# dist_sensor.net
KiCad netlist of a schematic drawn in EAGLE
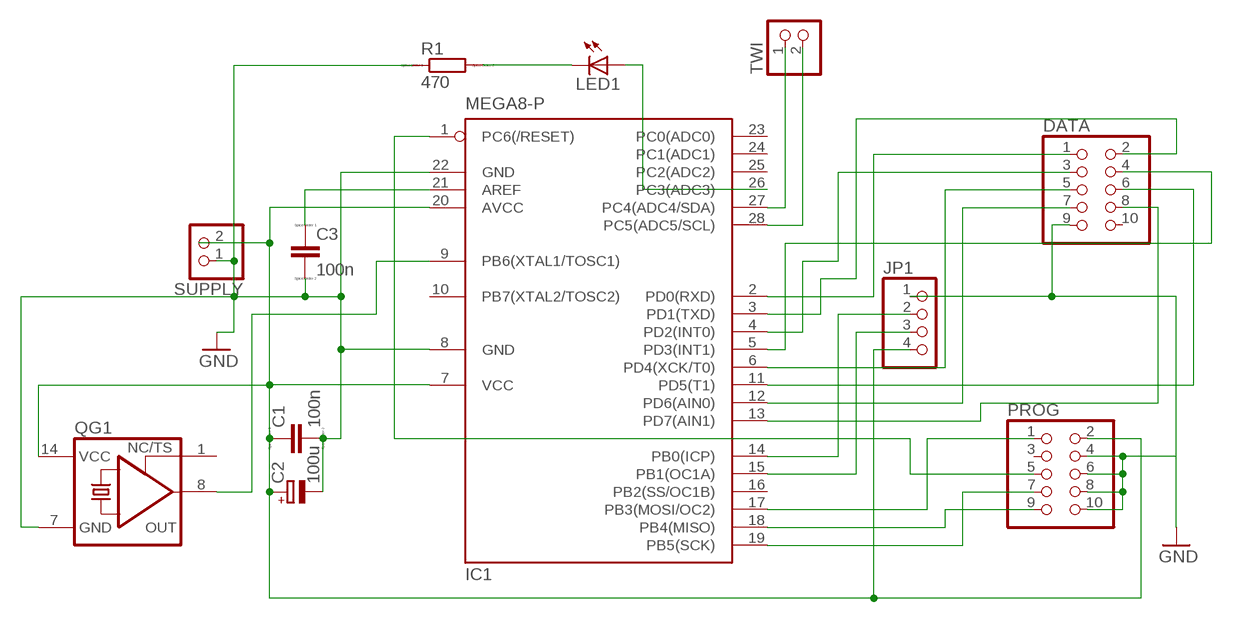
[diagram p0: schematic, sheet 1]

(export (version "E")
  (design (tool "Eeschema 10.0.6"))
  (components
    (comp (ref "C1")
      (value "100n")
      (footprint "eagle-import:C025-025X050")
      (libsource (lib "eagle-import") (part "C-EU025-025X050"))
    )
    (comp (ref "C2")
      (value "100u")
      (footprint "eagle-import:E5-8,5")
      (libsource (lib "eagle-import") (part "CPOL-EUE5-8.5"))
    )
    (comp (ref "C3")
      (value "100n")
      (footprint "eagle-import:C025-025X050")
      (libsource (lib "eagle-import") (part "C-EU025-025X050"))
    )
    (comp (ref "DATA")
      (value "PINHD-2X5")
      (footprint "eagle-import:2X05")
      (libsource (lib "eagle-import") (part "PINHD-2X5"))
    )
    (comp (ref "IC1")
      (value "MEGA8-P")
      (footprint "eagle-import:DIL28-3")
      (libsource (lib "eagle-import") (part "MEGA8-P"))
    )
    (comp (ref "JP1")
      (value "PINHD-1X4")
      (footprint "eagle-import:1X04")
      (libsource (lib "eagle-import") (part "PINHD-1X4"))
    )
    (comp (ref "LED1")
      (value "LED5MM")
      (footprint "eagle-import:LED5MM")
      (libsource (lib "eagle-import") (part "LED5MM"))
    )
    (comp (ref "PROG")
      (value "PINHD-2X5")
      (footprint "eagle-import:2X05")
      (libsource (lib "eagle-import") (part "PINHD-2X5"))
    )
    (comp (ref "QG1")
      (value "XO-14")
      (footprint "eagle-import:DIL14S")
      (libsource (lib "eagle-import") (part "XO-14"))
    )
    (comp (ref "R1")
      (value "470")
      (footprint "eagle-import:0207_10")
      (libsource (lib "eagle-import") (part "R-EU_0207_10"))
    )
    (comp (ref "SUPPLY")
      (value "PINHD-1X2")
      (footprint "eagle-import:1X02")
      (libsource (lib "eagle-import") (part "PINHD-1X2"))
    )
    (comp (ref "TWI")
      (value "PINHD-1X2")
      (footprint "eagle-import:1X02")
      (libsource (lib "eagle-import") (part "PINHD-1X2"))
    )
  )
  (nets
    (net (code "1") (name "GND") (class "Default")
      (node (ref "C1") (pin "2") (pinfunction "2_2") (pintype "passive"))
      (node (ref "C2") (pin "-") (pinfunction "-_-") (pintype "passive"))
      (node (ref "C3") (pin "2") (pinfunction "2_2") (pintype "passive"))
      (node (ref "DATA") (pin "9") (pinfunction "9_9") (pintype "passive"))
      (node (ref "IC1") (pin "22") (pinfunction "GND_22") (pintype "power_in"))
      (node (ref "IC1") (pin "8") (pinfunction "GND_8") (pintype "power_in"))
      (node (ref "JP1") (pin "1") (pinfunction "1_1") (pintype "passive"))
      (node (ref "PROG") (pin "10") (pinfunction "10_10") (pintype "passive"))
      (node (ref "PROG") (pin "4") (pinfunction "4_4") (pintype "passive"))
      (node (ref "PROG") (pin "6") (pinfunction "6_6") (pintype "passive"))
      (node (ref "PROG") (pin "8") (pinfunction "8_8") (pintype "passive"))
      (node (ref "QG1") (pin "7") (pinfunction "GND_7") (pintype "power_in"))
      (node (ref "R1") (pin "1") (pinfunction "1_1") (pintype "passive"))
      (node (ref "SUPPLY") (pin "1") (pinfunction "1_1") (pintype "passive"))
    )
    (net (code "2") (name "Net-(IC1-AREF)") (class "Default")
      (node (ref "C3") (pin "1") (pinfunction "1_1") (pintype "passive"))
      (node (ref "IC1") (pin "21") (pinfunction "AREF_21") (pintype "passive"))
    )
    (net (code "3") (name "Net-(IC1-AVCC)") (class "Default")
      (node (ref "C1") (pin "1") (pinfunction "1_1") (pintype "passive"))
      (node (ref "C2") (pin "+") (pinfunction "+_+") (pintype "passive"))
      (node (ref "IC1") (pin "20") (pinfunction "AVCC_20") (pintype "power_in"))
      (node (ref "IC1") (pin "7") (pinfunction "VCC_7") (pintype "power_in"))
      (node (ref "JP1") (pin "4") (pinfunction "4_4") (pintype "passive"))
      (node (ref "PROG") (pin "2") (pinfunction "2_2") (pintype "passive"))
      (node (ref "QG1") (pin "14") (pinfunction "VCC_14") (pintype "power_in"))
      (node (ref "SUPPLY") (pin "2") (pinfunction "2_2") (pintype "passive"))
    )
    (net (code "4") (name "Net-(IC1-PB0(ICP))") (class "Default")
      (node (ref "IC1") (pin "14") (pinfunction "PB0(ICP)_14") (pintype "bidirectional"))
      (node (ref "JP1") (pin "2") (pinfunction "2_2") (pintype "passive"))
    )
    (net (code "5") (name "Net-(IC1-PB1(OC1A))") (class "Default")
      (node (ref "IC1") (pin "15") (pinfunction "PB1(OC1A)_15") (pintype "bidirectional"))
      (node (ref "JP1") (pin "3") (pinfunction "3_3") (pintype "passive"))
    )
    (net (code "6") (name "Net-(IC1-PB3(MOSI{slash}OC2))") (class "Default")
      (node (ref "IC1") (pin "17") (pinfunction "PB3(MOSI/OC2)_17") (pintype "bidirectional"))
      (node (ref "PROG") (pin "1") (pinfunction "1_1") (pintype "passive"))
    )
    (net (code "7") (name "Net-(IC1-PB4(MISO))") (class "Default")
      (node (ref "IC1") (pin "18") (pinfunction "PB4(MISO)_18") (pintype "bidirectional"))
      (node (ref "PROG") (pin "9") (pinfunction "9_9") (pintype "passive"))
    )
    (net (code "8") (name "Net-(IC1-PB5(SCK))") (class "Default")
      (node (ref "IC1") (pin "19") (pinfunction "PB5(SCK)_19") (pintype "bidirectional"))
      (node (ref "PROG") (pin "7") (pinfunction "7_7") (pintype "passive"))
    )
    (net (code "9") (name "Net-(IC1-PB6(XTAL1{slash}TOSC1))") (class "Default")
      (node (ref "IC1") (pin "9") (pinfunction "PB6(XTAL1/TOSC1)_9") (pintype "bidirectional"))
      (node (ref "QG1") (pin "8") (pinfunction "OUT_8") (pintype "output"))
    )
    (net (code "10") (name "Net-(IC1-PC3(ADC3))") (class "Default")
      (node (ref "IC1") (pin "26") (pinfunction "PC3(ADC3)_26") (pintype "bidirectional"))
      (node (ref "LED1") (pin "A") (pinfunction "A_A") (pintype "passive"))
    )
    (net (code "11") (name "Net-(IC1-PC4(ADC4{slash}SDA))") (class "Default")
      (node (ref "IC1") (pin "27") (pinfunction "PC4(ADC4/SDA)_27") (pintype "bidirectional"))
      (node (ref "TWI") (pin "1") (pinfunction "1_1") (pintype "passive"))
    )
    (net (code "12") (name "Net-(IC1-PC5(ADC5{slash}SCL))") (class "Default")
      (node (ref "IC1") (pin "28") (pinfunction "PC5(ADC5/SCL)_28") (pintype "bidirectional"))
      (node (ref "TWI") (pin "2") (pinfunction "2_2") (pintype "passive"))
    )
    (net (code "13") (name "Net-(IC1-PC6({slash}RESET))") (class "Default")
      (node (ref "IC1") (pin "1") (pinfunction "PC6(/RESET)_1") (pintype "bidirectional"))
      (node (ref "PROG") (pin "5") (pinfunction "5_5") (pintype "passive"))
    )
    (net (code "14") (name "Net-(IC1-PD0(RXD))") (class "Default")
      (node (ref "DATA") (pin "1") (pinfunction "1_1") (pintype "passive"))
      (node (ref "IC1") (pin "2") (pinfunction "PD0(RXD)_2") (pintype "bidirectional"))
    )
    (net (code "15") (name "Net-(IC1-PD1(TXD))") (class "Default")
      (node (ref "DATA") (pin "2") (pinfunction "2_2") (pintype "passive"))
      (node (ref "IC1") (pin "3") (pinfunction "PD1(TXD)_3") (pintype "bidirectional"))
    )
    (net (code "16") (name "Net-(IC1-PD2(INT0))") (class "Default")
      (node (ref "DATA") (pin "3") (pinfunction "3_3") (pintype "passive"))
      (node (ref "IC1") (pin "4") (pinfunction "PD2(INT0)_4") (pintype "bidirectional"))
    )
    (net (code "17") (name "Net-(IC1-PD3(INT1))") (class "Default")
      (node (ref "DATA") (pin "4") (pinfunction "4_4") (pintype "passive"))
      (node (ref "IC1") (pin "5") (pinfunction "PD3(INT1)_5") (pintype "bidirectional"))
    )
    (net (code "18") (name "Net-(IC1-PD4(XCK{slash}T0))") (class "Default")
      (node (ref "DATA") (pin "5") (pinfunction "5_5") (pintype "passive"))
      (node (ref "IC1") (pin "6") (pinfunction "PD4(XCK/T0)_6") (pintype "bidirectional"))
    )
    (net (code "19") (name "Net-(IC1-PD5(T1))") (class "Default")
      (node (ref "DATA") (pin "6") (pinfunction "6_6") (pintype "passive"))
      (node (ref "IC1") (pin "11") (pinfunction "PD5(T1)_11") (pintype "bidirectional"))
    )
    (net (code "20") (name "Net-(IC1-PD6(AIN0))") (class "Default")
      (node (ref "DATA") (pin "7") (pinfunction "7_7") (pintype "passive"))
      (node (ref "IC1") (pin "12") (pinfunction "PD6(AIN0)_12") (pintype "bidirectional"))
    )
    (net (code "21") (name "Net-(IC1-PD7(AIN1))") (class "Default")
      (node (ref "DATA") (pin "8") (pinfunction "8_8") (pintype "passive"))
      (node (ref "IC1") (pin "13") (pinfunction "PD7(AIN1)_13") (pintype "bidirectional"))
    )
    (net (code "22") (name "Net-(LED1-C)") (class "Default")
      (node (ref "LED1") (pin "K") (pinfunction "C_K") (pintype "passive"))
      (node (ref "R1") (pin "2") (pinfunction "2_2") (pintype "passive"))
    )
    (net (code "23") (name "unconnected-(DATA-Pad10)") (class "Default")
      (node (ref "DATA") (pin "10") (pinfunction "10_10") (pintype "passive"))
    )
    (net (code "24") (name "unconnected-(IC1-PB2(SS{slash}OC1B)-Pad16)") (class "Default")
      (node (ref "IC1") (pin "16") (pinfunction "PB2(SS/OC1B)_16") (pintype "bidirectional"))
    )
    (net (code "25") (name "unconnected-(IC1-PB7(XTAL2{slash}TOSC2)-Pad10)") (class "Default")
      (node (ref "IC1") (pin "10") (pinfunction "PB7(XTAL2/TOSC2)_10") (pintype "bidirectional"))
    )
    (net (code "26") (name "unconnected-(IC1-PC0(ADC0)-Pad23)") (class "Default")
      (node (ref "IC1") (pin "23") (pinfunction "PC0(ADC0)_23") (pintype "bidirectional"))
    )
    (net (code "27") (name "unconnected-(IC1-PC1(ADC1)-Pad24)") (class "Default")
      (node (ref "IC1") (pin "24") (pinfunction "PC1(ADC1)_24") (pintype "bidirectional"))
    )
    (net (code "28") (name "unconnected-(IC1-PC2(ADC2)-Pad25)") (class "Default")
      (node (ref "IC1") (pin "25") (pinfunction "PC2(ADC2)_25") (pintype "bidirectional"))
    )
    (net (code "29") (name "unconnected-(PROG-Pad3)") (class "Default")
      (node (ref "PROG") (pin "3") (pinfunction "3_3") (pintype "passive"))
    )
    (net (code "30") (name "unconnected-(QG1-TS-Pad1)") (class "Default")
      (node (ref "QG1") (pin "1") (pinfunction "TS_1") (pintype "passive"))
    )
  )
)
